# rgb-led-a1.net
KiCad netlist of a schematic drawn in EAGLE
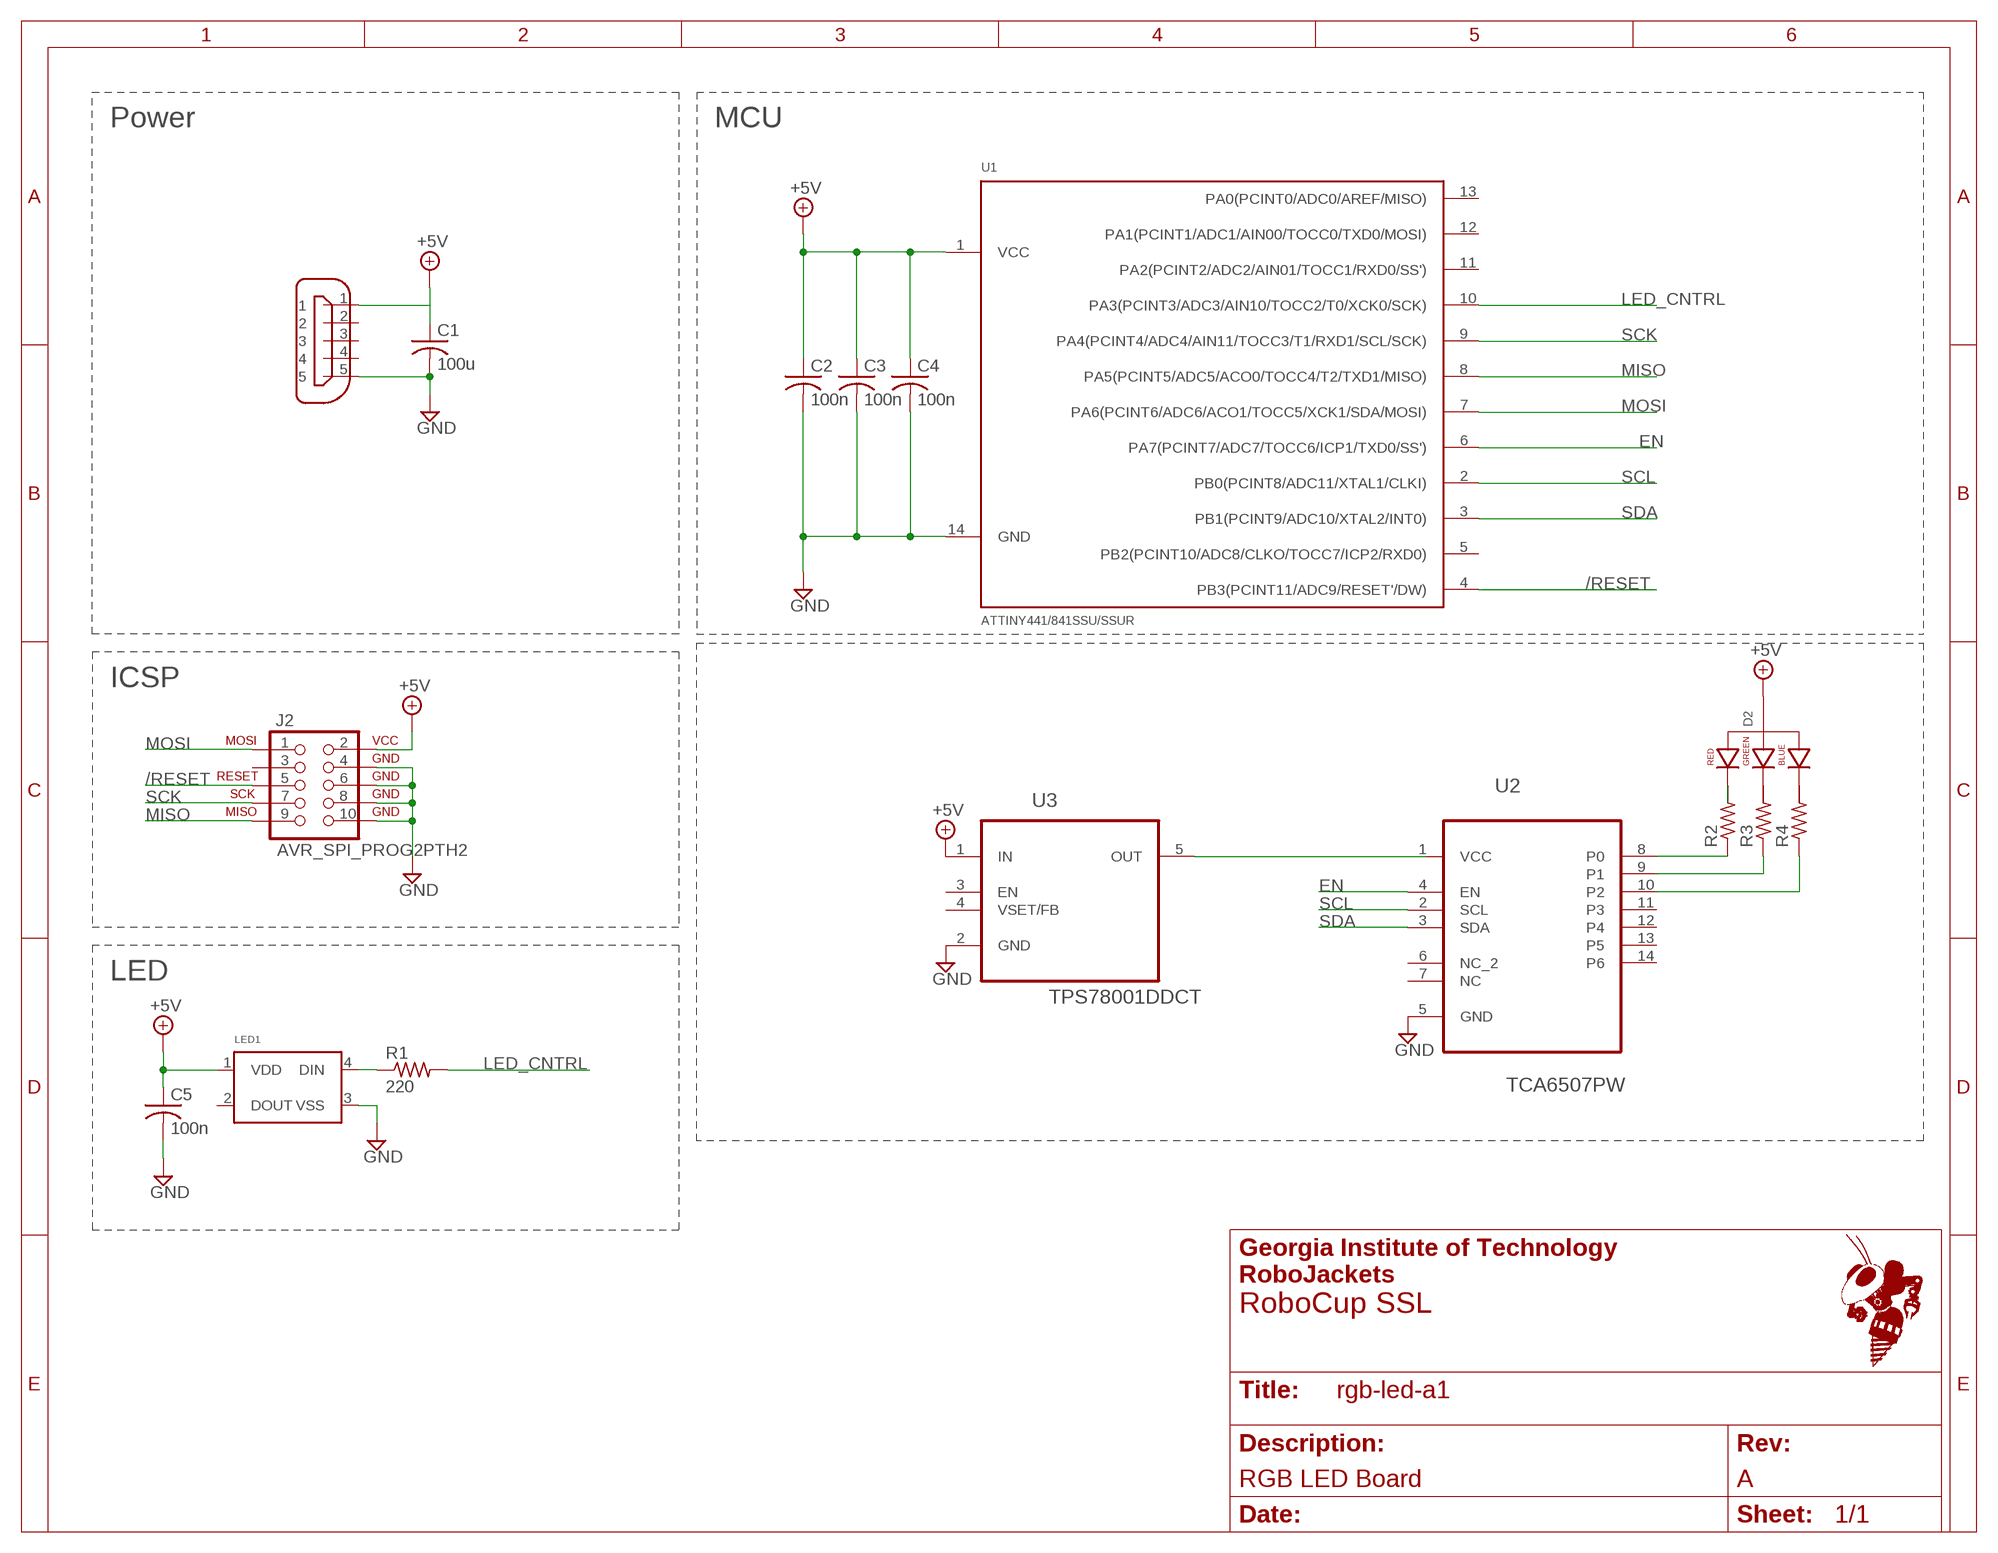
[diagram p0: schematic, sheet 1]

(export (version "E")
  (design (tool "Eeschema 10.0.6"))
  (components
    (comp (ref "C1")
      (value "100u")
      (footprint "eagle-import:C1206")
      (libsource (lib "eagle-import") (part "C-USC1206"))
    )
    (comp (ref "C2")
      (value "100n")
      (footprint "eagle-import:C0603")
      (libsource (lib "eagle-import") (part "C-USC0603"))
    )
    (comp (ref "C3")
      (value "100n")
      (footprint "eagle-import:C0603")
      (libsource (lib "eagle-import") (part "C-USC0603"))
    )
    (comp (ref "C4")
      (value "100n")
      (footprint "eagle-import:C0603")
      (libsource (lib "eagle-import") (part "C-USC0603"))
    )
    (comp (ref "C5")
      (value "100n")
      (footprint "eagle-import:C0603")
      (libsource (lib "eagle-import") (part "C-USC0603"))
    )
    (comp (ref "D2")
      (value "LED-RGB-CA-THRUCLEAR")
      (footprint "eagle-import:LED-RGB-THRU")
      (libsource (lib "eagle-import") (part "LED-RGB-CA-THRUCLEAR"))
    )
    (comp (ref "J1")
      (value "MICRO-USB")
      (footprint "eagle-import:GS-14-2180")
      (libsource (lib "eagle-import") (part "MICRO-USB"))
    )
    (comp (ref "J2")
      (value "AVR_SPI_PROG2PTH2")
      (footprint "eagle-import:2X5-SHROUDED")
      (libsource (lib "eagle-import") (part "AVR_SPI_PROG2PTH2"))
    )
    (comp (ref "LED1")
      (value "WS2812B")
      (footprint "eagle-import:5050")
      (libsource (lib "eagle-import") (part "WS2812B"))
    )
    (comp (ref "R1")
      (value "220")
      (footprint "eagle-import:R0603")
      (libsource (lib "eagle-import") (part "R-US_R0603"))
    )
    (comp (ref "R2")
      (value "R-US_R0805")
      (footprint "eagle-import:R0805")
      (libsource (lib "eagle-import") (part "resistor_R-US_R0805"))
    )
    (comp (ref "R3")
      (value "R-US_R0805")
      (footprint "eagle-import:R0805")
      (libsource (lib "eagle-import") (part "resistor_R-US_R0805"))
    )
    (comp (ref "R4")
      (value "R-US_R0805")
      (footprint "eagle-import:R0805")
      (libsource (lib "eagle-import") (part "resistor_R-US_R0805"))
    )
    (comp (ref "U1")
      (value "ATTINY441/841SSU/SSUR")
      (footprint "eagle-import:SOIC-14")
      (libsource (lib "eagle-import") (part "ATTINY441/841SSU/SSUR"))
    )
    (comp (ref "U2")
      (value "TCA6507PW")
      (footprint "eagle-import:SOP65P640X120-14N")
      (libsource (lib "eagle-import") (part "TCA6507PW"))
    )
    (comp (ref "U3")
      (value "TPS78001DDCT")
      (footprint "eagle-import:SOT95P280X110-5N")
      (libsource (lib "eagle-import") (part "TPS78001DDCT"))
    )
  )
  (nets
    (net (code "1") (name "+5V") (class "Default")
      (node (ref "C1") (pin "1") (pinfunction "1_1") (pintype "passive"))
      (node (ref "C2") (pin "1") (pinfunction "1_1") (pintype "passive"))
      (node (ref "C3") (pin "1") (pinfunction "1_1") (pintype "passive"))
      (node (ref "C4") (pin "1") (pinfunction "1_1") (pintype "passive"))
      (node (ref "C5") (pin "1") (pinfunction "1_1") (pintype "passive"))
      (node (ref "D2") (pin "2") (pinfunction "ANODE_2") (pintype "bidirectional"))
      (node (ref "J1") (pin "1") (pinfunction "1_1") (pintype "bidirectional"))
      (node (ref "J2") (pin "2") (pinfunction "VCC_2") (pintype "power_in"))
      (node (ref "LED1") (pin "1") (pinfunction "VDD_1") (pintype "bidirectional"))
      (node (ref "U1") (pin "1") (pinfunction "VCC_1") (pintype "bidirectional"))
      (node (ref "U3") (pin "1") (pinfunction "IN_1") (pintype "power_in"))
    )
    (net (code "2") (name "/EN") (class "Default")
      (node (ref "U1") (pin "6") (pinfunction "PA7(PCINT7/ADC7/TOCC6/ICP1/TXD0/SS')_6") (pintype "bidirectional"))
      (node (ref "U2") (pin "4") (pinfunction "EN_4") (pintype "input"))
    )
    (net (code "3") (name "/LED_CNTRL") (class "Default")
      (node (ref "R1") (pin "2") (pinfunction "2_2") (pintype "passive"))
      (node (ref "U1") (pin "10") (pinfunction "PA3(PCINT3/ADC3/AIN10/TOCC2/T0/XCK0/SCK)_10") (pintype "bidirectional"))
    )
    (net (code "4") (name "/MISO") (class "Default")
      (node (ref "J2") (pin "9") (pinfunction "MISO_9") (pintype "passive"))
      (node (ref "U1") (pin "8") (pinfunction "PA5(PCINT5/ADC5/ACO0/TOCC4/T2/TXD1/MISO)_8") (pintype "bidirectional"))
    )
    (net (code "5") (name "/MOSI") (class "Default")
      (node (ref "J2") (pin "1") (pinfunction "MOSI_1") (pintype "passive"))
      (node (ref "U1") (pin "7") (pinfunction "PA6(PCINT6/ADC6/ACO1/TOCC5/XCK1/SDA/MOSI)_7") (pintype "bidirectional"))
    )
    (net (code "6") (name "/SCK") (class "Default")
      (node (ref "J2") (pin "7") (pinfunction "SCK_7") (pintype "passive"))
      (node (ref "U1") (pin "9") (pinfunction "PA4(PCINT4/ADC4/AIN11/TOCC3/T1/RXD1/SCL/SCK)_9") (pintype "bidirectional"))
    )
    (net (code "7") (name "/SCL") (class "Default")
      (node (ref "U1") (pin "2") (pinfunction "PB0(PCINT8/ADC11/XTAL1/CLKI)_2") (pintype "bidirectional"))
      (node (ref "U2") (pin "2") (pinfunction "SCL_2") (pintype "input"))
    )
    (net (code "8") (name "/SDA") (class "Default")
      (node (ref "U1") (pin "3") (pinfunction "PB1(PCINT9/ADC10/XTAL2/INT0)_3") (pintype "bidirectional"))
      (node (ref "U2") (pin "3") (pinfunction "SDA_3") (pintype "input"))
    )
    (net (code "9") (name "/VCC") (class "Default")
      (node (ref "U2") (pin "1") (pinfunction "VCC_1") (pintype "power_in"))
    )
    (net (code "10") (name "/{slash}RESET") (class "Default")
      (node (ref "J2") (pin "5") (pinfunction "RESET_5") (pintype "passive"))
      (node (ref "U1") (pin "4") (pinfunction "PB3(PCINT11/ADC9/RESET'/DW)_4") (pintype "bidirectional"))
    )
    (net (code "11") (name "GND") (class "Default")
      (node (ref "C1") (pin "2") (pinfunction "2_2") (pintype "passive"))
      (node (ref "C2") (pin "2") (pinfunction "2_2") (pintype "passive"))
      (node (ref "C3") (pin "2") (pinfunction "2_2") (pintype "passive"))
      (node (ref "C4") (pin "2") (pinfunction "2_2") (pintype "passive"))
      (node (ref "C5") (pin "2") (pinfunction "2_2") (pintype "passive"))
      (node (ref "J1") (pin "5") (pinfunction "5_5") (pintype "bidirectional"))
      (node (ref "J2") (pin "10") (pinfunction "GND_10") (pintype "power_in"))
      (node (ref "J2") (pin "4") (pinfunction "GND_4") (pintype "power_in"))
      (node (ref "J2") (pin "6") (pinfunction "GND_6") (pintype "power_in"))
      (node (ref "J2") (pin "8") (pinfunction "GND_8") (pintype "power_in"))
      (node (ref "LED1") (pin "3") (pinfunction "VSS_3") (pintype "bidirectional"))
      (node (ref "U1") (pin "14") (pinfunction "GND_14") (pintype "bidirectional"))
      (node (ref "U2") (pin "5") (pinfunction "GND_5") (pintype "passive"))
      (node (ref "U3") (pin "2") (pinfunction "GND_2") (pintype "passive"))
    )
    (net (code "12") (name "Net-(D2-RED_CATHODE)") (class "Default")
      (node (ref "D2") (pin "1") (pinfunction "RED_CATHODE_1") (pintype "bidirectional"))
      (node (ref "R2") (pin "2") (pinfunction "2_2") (pintype "passive"))
    )
    (net (code "13") (name "Net-(LED1-DIN)") (class "Default")
      (node (ref "LED1") (pin "4") (pinfunction "DIN_4") (pintype "bidirectional"))
      (node (ref "R1") (pin "1") (pinfunction "1_1") (pintype "passive"))
    )
    (net (code "14") (name "Net-(U2-P0)") (class "Default")
      (node (ref "R2") (pin "1") (pinfunction "1_1") (pintype "passive"))
      (node (ref "U2") (pin "8") (pinfunction "P0_8") (pintype "output"))
    )
    (net (code "15") (name "Net-(U2-P1)") (class "Default")
      (node (ref "R3") (pin "1") (pinfunction "1_1") (pintype "passive"))
      (node (ref "U2") (pin "9") (pinfunction "P1_9") (pintype "output"))
    )
    (net (code "16") (name "Net-(U2-P2)") (class "Default")
      (node (ref "R4") (pin "1") (pinfunction "1_1") (pintype "passive"))
      (node (ref "U2") (pin "10") (pinfunction "P2_10") (pintype "output"))
    )
    (net (code "17") (name "unconnected-(D2-BLUE_CATHODE-Pad4)") (class "Default")
      (node (ref "D2") (pin "4") (pinfunction "BLUE_CATHODE_4") (pintype "bidirectional"))
    )
    (net (code "18") (name "unconnected-(D2-GREEN_CATHODE-Pad3)") (class "Default")
      (node (ref "D2") (pin "3") (pinfunction "GREEN_CATHODE_3") (pintype "bidirectional"))
    )
    (net (code "19") (name "unconnected-(J1-Pad2)") (class "Default")
      (node (ref "J1") (pin "2") (pinfunction "2_2") (pintype "bidirectional"))
    )
    (net (code "20") (name "unconnected-(J1-Pad3)") (class "Default")
      (node (ref "J1") (pin "3") (pinfunction "3_3") (pintype "bidirectional"))
    )
    (net (code "21") (name "unconnected-(J1-Pad4)") (class "Default")
      (node (ref "J1") (pin "4") (pinfunction "4_4") (pintype "bidirectional"))
    )
    (net (code "22") (name "unconnected-(J2-NC-Pad3)") (class "Default")
      (node (ref "J2") (pin "3") (pinfunction "NC_3") (pintype "no_connect"))
    )
    (net (code "23") (name "unconnected-(LED1-DOUT-Pad2)") (class "Default")
      (node (ref "LED1") (pin "2") (pinfunction "DOUT_2") (pintype "bidirectional"))
    )
    (net (code "24") (name "unconnected-(R3-Pad2)") (class "Default")
      (node (ref "R3") (pin "2") (pinfunction "2_2") (pintype "passive"))
    )
    (net (code "25") (name "unconnected-(R4-Pad2)") (class "Default")
      (node (ref "R4") (pin "2") (pinfunction "2_2") (pintype "passive"))
    )
    (net (code "26") (name "unconnected-(U1-PA0(PCINT0{slash}ADC0{slash}AREF{slash}MISO)-Pad13)") (class "Default")
      (node (ref "U1") (pin "13") (pinfunction "PA0(PCINT0/ADC0/AREF/MISO)_13") (pintype "bidirectional"))
    )
    (net (code "27") (name "unconnected-(U1-PA1(PCINT1{slash}ADC1{slash}AIN00{slash}TOCC0{slash}TXD0{slash}MOSI)-Pad12)") (class "Default")
      (node (ref "U1") (pin "12") (pinfunction "PA1(PCINT1/ADC1/AIN00/TOCC0/TXD0/MOSI)_12") (pintype "bidirectional"))
    )
    (net (code "28") (name "unconnected-(U1-PA2(PCINT2{slash}ADC2{slash}AIN01{slash}TOCC1{slash}RXD0{slash}SS')-Pad11)") (class "Default")
      (node (ref "U1") (pin "11") (pinfunction "PA2(PCINT2/ADC2/AIN01/TOCC1/RXD0/SS')_11") (pintype "bidirectional"))
    )
    (net (code "29") (name "unconnected-(U1-PB2(PCINT10{slash}ADC8{slash}CLKO{slash}TOCC7{slash}ICP2{slash}RXD0)-Pad5)") (class "Default")
      (node (ref "U1") (pin "5") (pinfunction "PB2(PCINT10/ADC8/CLKO/TOCC7/ICP2/RXD0)_5") (pintype "bidirectional"))
    )
    (net (code "30") (name "unconnected-(U2-NC-Pad7)") (class "Default")
      (node (ref "U2") (pin "7") (pinfunction "NC_7") (pintype "no_connect"))
    )
    (net (code "31") (name "unconnected-(U2-NC_2-Pad6)") (class "Default")
      (node (ref "U2") (pin "6") (pinfunction "NC_2_6") (pintype "no_connect"))
    )
    (net (code "32") (name "unconnected-(U2-P3-Pad11)") (class "Default")
      (node (ref "U2") (pin "11") (pinfunction "P3_11") (pintype "output"))
    )
    (net (code "33") (name "unconnected-(U2-P4-Pad12)") (class "Default")
      (node (ref "U2") (pin "12") (pinfunction "P4_12") (pintype "output"))
    )
    (net (code "34") (name "unconnected-(U2-P5-Pad13)") (class "Default")
      (node (ref "U2") (pin "13") (pinfunction "P5_13") (pintype "output"))
    )
    (net (code "35") (name "unconnected-(U2-P6-Pad14)") (class "Default")
      (node (ref "U2") (pin "14") (pinfunction "P6_14") (pintype "output"))
    )
    (net (code "36") (name "unconnected-(U3-EN-Pad3)") (class "Default")
      (node (ref "U3") (pin "3") (pinfunction "EN_3") (pintype "input"))
    )
    (net (code "37") (name "unconnected-(U3-OUT-Pad5)") (class "Default")
      (node (ref "U3") (pin "5") (pinfunction "OUT_5") (pintype "output"))
    )
    (net (code "38") (name "unconnected-(U3-VSET{slash}FB-Pad4)") (class "Default")
      (node (ref "U3") (pin "4") (pinfunction "VSET/FB_4") (pintype "input"))
    )
  )
)
